# WaterLevel-STM8-V2.net
KiCad netlist of a schematic drawn in EAGLE
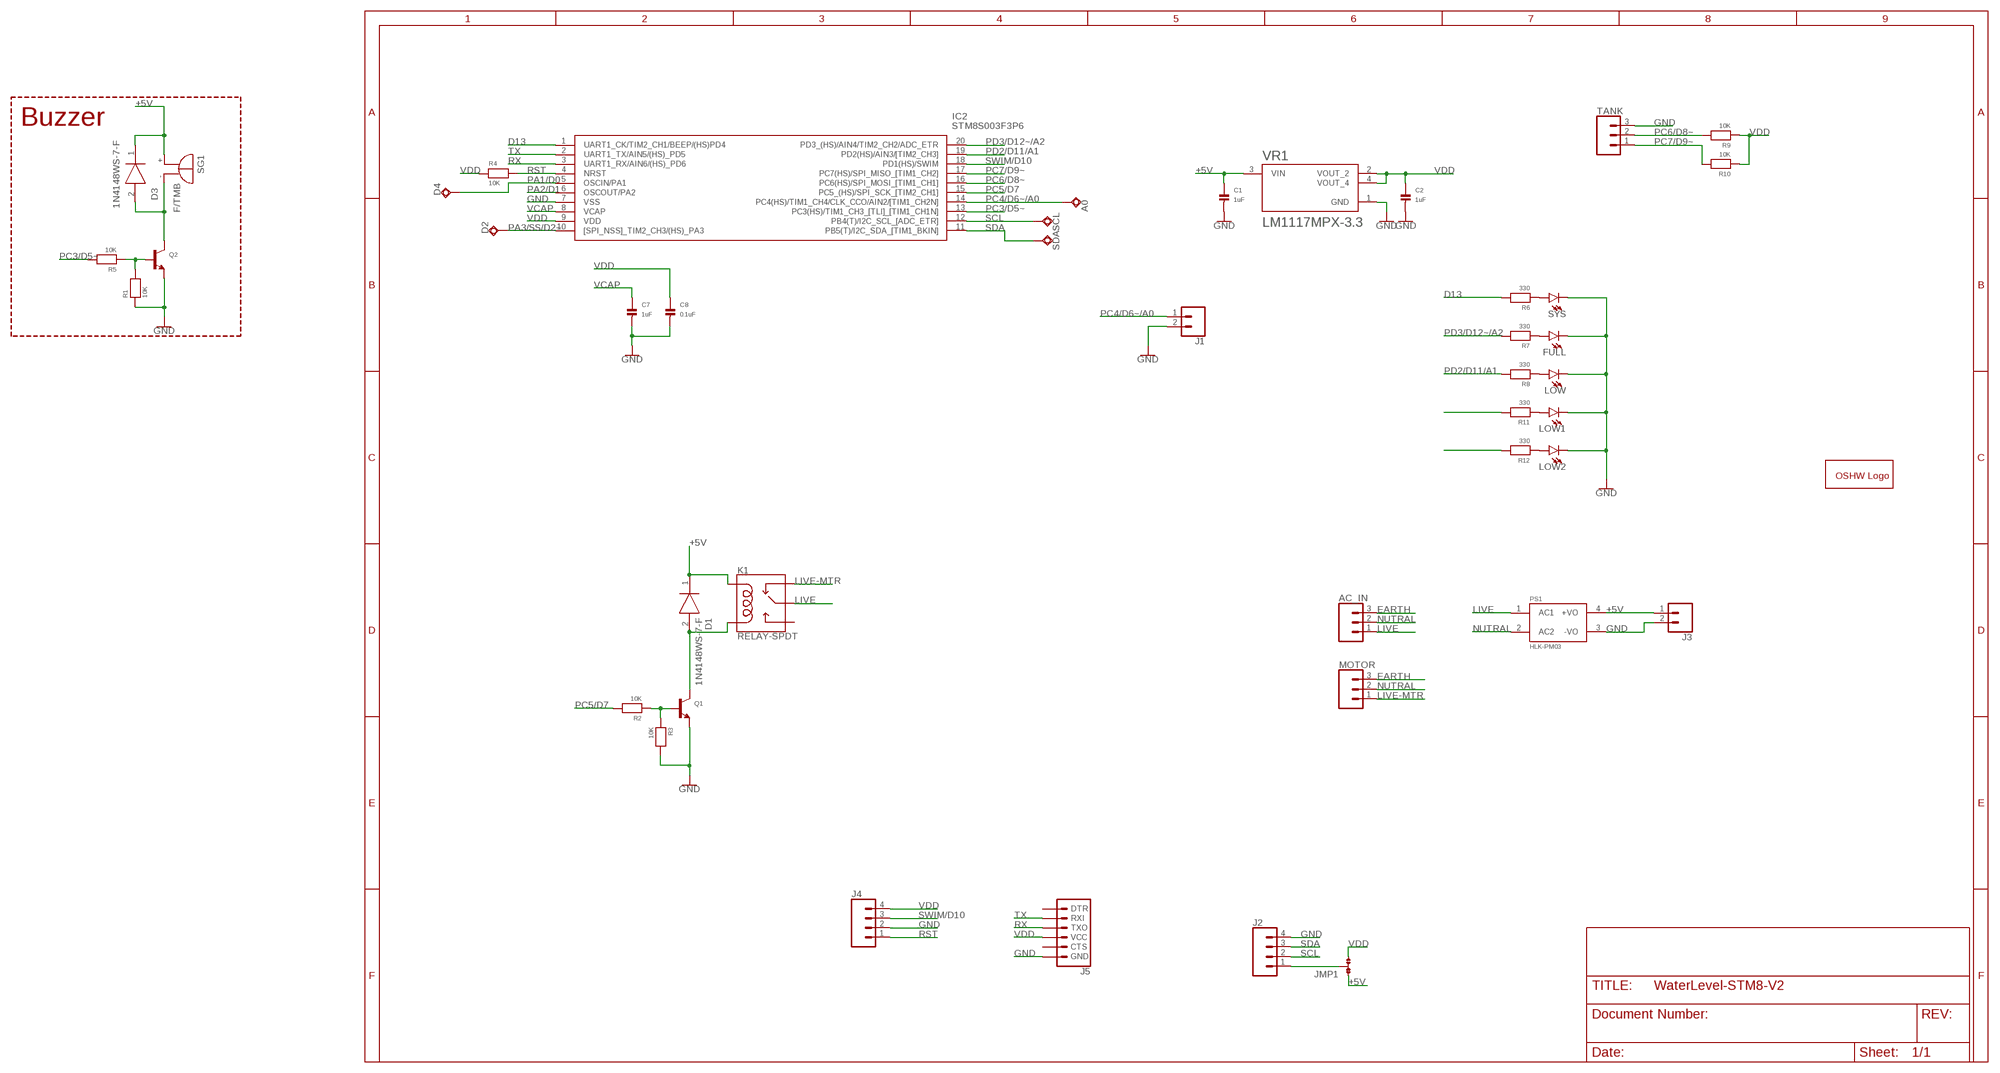
[diagram p0: schematic, sheet 1]

(export (version "E")
  (design (tool "Eeschema 10.0.6"))
  (components
    (comp (ref "A0")
      (value "TPSQTP20R")
      (footprint "eagle-import:TP20R")
      (libsource (lib "eagle-import") (part "TPSQTP20R"))
    )
    (comp (ref "AC_IN")
      (value "SCREW-CONN_03-SCREW-5MM")
      (footprint "eagle-import:SCREWTERMINAL-5MM-3")
      (libsource (lib "eagle-import") (part "SCREW-CONN_03-SCREW-5MM"))
    )
    (comp (ref "C1")
      (value "1uF")
      (footprint "eagle-import:C0805")
      (libsource (lib "eagle-import") (part "CAP_CERAMIC0805"))
    )
    (comp (ref "C2")
      (value "1uF")
      (footprint "eagle-import:C0805")
      (libsource (lib "eagle-import") (part "CAP_CERAMIC0805"))
    )
    (comp (ref "C7")
      (value "1uF")
      (footprint "eagle-import:C0805")
      (libsource (lib "eagle-import") (part "CAP_CERAMIC0805"))
    )
    (comp (ref "C8")
      (value "0.1uF")
      (footprint "eagle-import:C0805")
      (libsource (lib "eagle-import") (part "CAP_CERAMIC0805"))
    )
    (comp (ref "D1")
      (value "1N4148WS-7-F")
      (footprint "eagle-import:SOD2513X120N")
      (fields (field (name "MOUSER_PART_NUMBER") "621-1N4148WS-F"))
      (libsource (lib "eagle-import") (part "1N4148WS-7-F"))
    )
    (comp (ref "D2")
      (value "TPSQTP20R")
      (footprint "eagle-import:TP20R")
      (libsource (lib "eagle-import") (part "TPSQTP20R"))
    )
    (comp (ref "D3")
      (value "1N4148WS-7-F")
      (footprint "eagle-import:SOD2513X120N")
      (fields (field (name "MOUSER_PART_NUMBER") "621-1N4148WS-F"))
      (libsource (lib "eagle-import") (part "1N4148WS-7-F"))
    )
    (comp (ref "D4")
      (value "TPSQTP20R")
      (footprint "eagle-import:TP20R")
      (libsource (lib "eagle-import") (part "TPSQTP20R"))
    )
    (comp (ref "FULL")
      (value "LED-5MM-REC5MM")
      (footprint "eagle-import:LED_5MM")
      (libsource (lib "eagle-import") (part "LED-5MM-REC5MM"))
    )
    (comp (ref "GOLD_ORB_SM1")
      (value "OSHWLOGOLOGO16MM")
      (footprint "eagle-import:OSHW_16MM")
      (libsource (lib "eagle-import") (part "OSHWLOGOLOGO16MM"))
    )
    (comp (ref "IC2")
      (value "STM8S003F3P6")
      (footprint "eagle-import:SOP65P640X120-20N")
      (fields (field (name "MOUSER_PART_NUMBER") "511-STM8S003F3P6"))
      (libsource (lib "eagle-import") (part "STM8S003F3P6"))
    )
    (comp (ref "J1")
      (value "2PIN-2.54MM-POLARPOLAR")
      (footprint "eagle-import:MOLEX-1X2")
      (libsource (lib "eagle-import") (part "2PIN-2.54MM-POLARPOLAR"))
    )
    (comp (ref "J2")
      (value "CONN_04PTH")
      (footprint "eagle-import:1X04")
      (libsource (lib "eagle-import") (part "CONN_04PTH"))
    )
    (comp (ref "J3")
      (value "2PIN-2.54MM-POLARPOLAR")
      (footprint "eagle-import:MOLEX-1X2")
      (libsource (lib "eagle-import") (part "2PIN-2.54MM-POLARPOLAR"))
    )
    (comp (ref "J4")
      (value "CONN_04PTH")
      (footprint "eagle-import:1X04")
      (libsource (lib "eagle-import") (part "CONN_04PTH"))
    )
    (comp (ref "J5")
      (value "6_PIN_SERIAL_TARGETSILK")
      (footprint "eagle-import:6_PIN_SERIAL_TARGET_SIDE_W_SILK")
      (libsource (lib "eagle-import") (part "6_PIN_SERIAL_TARGETSILK"))
    )
    (comp (ref "JMP1")
      (value "JMP-3-NO")
      (footprint "eagle-import:JMP-3-NO")
      (libsource (lib "eagle-import") (part "JMP-3-NO"))
    )
    (comp (ref "K1")
      (value "RELAY-SPDT")
      (footprint "eagle-import:RELAY_G5LE")
      (libsource (lib "eagle-import") (part "RELAY-SPDT"))
    )
    (comp (ref "LOW")
      (value "LED-5MM-REC5MM")
      (footprint "eagle-import:LED_5MM")
      (libsource (lib "eagle-import") (part "LED-5MM-REC5MM"))
    )
    (comp (ref "LOW1")
      (value "LED-5MM-REC5MM")
      (footprint "eagle-import:LED_5MM")
      (libsource (lib "eagle-import") (part "LED-5MM-REC5MM"))
    )
    (comp (ref "LOW2")
      (value "LED-5MM-REC5MM")
      (footprint "eagle-import:LED_5MM")
      (libsource (lib "eagle-import") (part "LED-5MM-REC5MM"))
    )
    (comp (ref "MOTOR")
      (value "SCREW-CONN_03-SCREW-5MM")
      (footprint "eagle-import:SCREWTERMINAL-5MM-3")
      (libsource (lib "eagle-import") (part "SCREW-CONN_03-SCREW-5MM"))
    )
    (comp (ref "PS1")
      (value "HLK-PM03")
      (footprint "eagle-import:CONV_HLK-PM03")
      (fields (field (name "MF") "Hi-link"))
      (libsource (lib "eagle-import") (part "HLK-PM03"))
    )
    (comp (ref "Q1")
      (value "TRANSISTOR_NPNWIDE")
      (footprint "eagle-import:SOT23-WIDE")
      (libsource (lib "eagle-import") (part "TRANSISTOR_NPNWIDE"))
    )
    (comp (ref "Q2")
      (value "TRANSISTOR_NPNWIDE")
      (footprint "eagle-import:SOT23-WIDE")
      (libsource (lib "eagle-import") (part "TRANSISTOR_NPNWIDE"))
    )
    (comp (ref "R1")
      (value "10K")
      (footprint "eagle-import:R0805")
      (libsource (lib "eagle-import") (part "RESISTOR0805"))
    )
    (comp (ref "R2")
      (value "10K")
      (footprint "eagle-import:R0805")
      (libsource (lib "eagle-import") (part "RESISTOR0805"))
    )
    (comp (ref "R3")
      (value "10K")
      (footprint "eagle-import:R0805")
      (libsource (lib "eagle-import") (part "RESISTOR0805"))
    )
    (comp (ref "R4")
      (value "10K")
      (footprint "eagle-import:R0805")
      (libsource (lib "eagle-import") (part "RESISTOR0805"))
    )
    (comp (ref "R5")
      (value "10K")
      (footprint "eagle-import:R0805")
      (libsource (lib "eagle-import") (part "RESISTOR0805"))
    )
    (comp (ref "R6")
      (value "330")
      (footprint "eagle-import:R0805")
      (libsource (lib "eagle-import") (part "RESISTOR0805"))
    )
    (comp (ref "R7")
      (value "330")
      (footprint "eagle-import:R0805")
      (libsource (lib "eagle-import") (part "RESISTOR0805"))
    )
    (comp (ref "R8")
      (value "330")
      (footprint "eagle-import:R0805")
      (libsource (lib "eagle-import") (part "RESISTOR0805"))
    )
    (comp (ref "R9")
      (value "10K")
      (footprint "eagle-import:R0805")
      (libsource (lib "eagle-import") (part "RESISTOR0805"))
    )
    (comp (ref "R10")
      (value "10K")
      (footprint "eagle-import:R0805")
      (libsource (lib "eagle-import") (part "RESISTOR0805"))
    )
    (comp (ref "R11")
      (value "330")
      (footprint "eagle-import:R0805")
      (libsource (lib "eagle-import") (part "RESISTOR0805"))
    )
    (comp (ref "R12")
      (value "330")
      (footprint "eagle-import:R0805")
      (libsource (lib "eagle-import") (part "RESISTOR0805"))
    )
    (comp (ref "SCL")
      (value "TPSQTP20R")
      (footprint "eagle-import:TP20R")
      (libsource (lib "eagle-import") (part "TPSQTP20R"))
    )
    (comp (ref "SDA")
      (value "TPSQTP20R")
      (footprint "eagle-import:TP20R")
      (libsource (lib "eagle-import") (part "TPSQTP20R"))
    )
    (comp (ref "SG1")
      (value "F/TMB")
      (footprint "eagle-import:F_TMB")
      (libsource (lib "eagle-import") (part "F/TMB"))
    )
    (comp (ref "SYS")
      (value "LED-5MM-REC5MM")
      (footprint "eagle-import:LED_5MM")
      (libsource (lib "eagle-import") (part "LED-5MM-REC5MM"))
    )
    (comp (ref "TANK")
      (value "SCREW-CONN_03-SCREW-5MM")
      (footprint "eagle-import:SCREWTERMINAL-5MM-3")
      (libsource (lib "eagle-import") (part "SCREW-CONN_03-SCREW-5MM"))
    )
    (comp (ref "VR1")
      (value "LM1117MPX-3.3")
      (footprint "eagle-import:VREG_LM1117MPX-3.3")
      (fields (field (name "MF") "Texas Instruments"))
      (libsource (lib "eagle-import") (part "LM1117MPX-3.3"))
    )
  )
  (nets
    (net (code "1") (name "/+5V") (class "Default")
      (node (ref "C1") (pin "1") (pinfunction "P$1_1") (pintype "passive"))
      (node (ref "D1") (pin "1") (pinfunction "K_1") (pintype "bidirectional"))
      (node (ref "D3") (pin "1") (pinfunction "K_1") (pintype "bidirectional"))
      (node (ref "J3") (pin "1") (pinfunction "1_1") (pintype "passive"))
      (node (ref "JMP1") (pin "1") (pinfunction "1_1") (pintype "passive"))
      (node (ref "K1") (pin "2") (pinfunction "COIL1_2") (pintype "bidirectional"))
      (node (ref "PS1") (pin "4") (pinfunction "+VO_4") (pintype "output"))
      (node (ref "SG1") (pin "+") (pinfunction "+_+") (pintype "passive"))
      (node (ref "VR1") (pin "3") (pinfunction "VIN_3") (pintype "input"))
    )
    (net (code "2") (name "/D13") (class "Default")
      (node (ref "IC2") (pin "1") (pinfunction "UART1_CK/TIM2_CH1/BEEP/(HS)PD4_1") (pintype "bidirectional"))
      (node (ref "R6") (pin "2") (pinfunction "2_2") (pintype "passive"))
    )
    (net (code "3") (name "/EARTH") (class "Default")
      (node (ref "AC_IN") (pin "3") (pinfunction "3_3") (pintype "passive"))
      (node (ref "MOTOR") (pin "3") (pinfunction "3_3") (pintype "passive"))
    )
    (net (code "4") (name "/LIVE") (class "Default")
      (node (ref "AC_IN") (pin "1") (pinfunction "1_1") (pintype "passive"))
      (node (ref "K1") (pin "1") (pinfunction "MAIN_1") (pintype "bidirectional"))
      (node (ref "PS1") (pin "1") (pinfunction "AC1_1") (pintype "input"))
    )
    (net (code "5") (name "/LIVE-MTR") (class "Default")
      (node (ref "K1") (pin "4") (pinfunction "NC_4") (pintype "bidirectional"))
      (node (ref "MOTOR") (pin "1") (pinfunction "1_1") (pintype "passive"))
    )
    (net (code "6") (name "/NUTRAL") (class "Default")
      (node (ref "AC_IN") (pin "2") (pinfunction "2_2") (pintype "passive"))
      (node (ref "MOTOR") (pin "2") (pinfunction "2_2") (pintype "passive"))
      (node (ref "PS1") (pin "2") (pinfunction "AC2_2") (pintype "input"))
    )
    (net (code "7") (name "/PA1{slash}D0") (class "Default")
      (node (ref "D4") (pin "TP") (pinfunction "TP_TP") (pintype "input"))
      (node (ref "IC2") (pin "5") (pinfunction "OSCIN/PA1_5") (pintype "input"))
    )
    (net (code "8") (name "/PA2{slash}D1") (class "Default")
      (node (ref "IC2") (pin "6") (pinfunction "OSCOUT/PA2_6") (pintype "output"))
    )
    (net (code "9") (name "/PA3{slash}SS{slash}D2~{}") (class "Default")
      (node (ref "D2") (pin "TP") (pinfunction "TP_TP") (pintype "input"))
      (node (ref "IC2") (pin "10") (pinfunction "[SPI_NSS]_TIM2_CH3/(HS)_PA3_10") (pintype "bidirectional"))
    )
    (net (code "10") (name "/PC3{slash}D5~{}") (class "Default")
      (node (ref "IC2") (pin "13") (pinfunction "PC3(HS)/TIM1_CH3_[TLI]_[TIM1_CH1N]_13") (pintype "bidirectional"))
      (node (ref "R5") (pin "2") (pinfunction "2_2") (pintype "passive"))
    )
    (net (code "11") (name "/PC4{slash}D6~{{slash}A0}") (class "Default")
      (node (ref "A0") (pin "TP") (pinfunction "TP_TP") (pintype "input"))
      (node (ref "IC2") (pin "14") (pinfunction "PC4(HS)/TIM1_CH4/CLK_CCO/AIN2/[TIM1_CH2N]_14") (pintype "input"))
      (node (ref "J1") (pin "1") (pinfunction "1_1") (pintype "passive"))
    )
    (net (code "12") (name "/PC5{slash}D7") (class "Default")
      (node (ref "IC2") (pin "15") (pinfunction "PC5_(HS)/SPI_SCK_[TIM2_CH1]_15") (pintype "bidirectional"))
      (node (ref "R2") (pin "2") (pinfunction "2_2") (pintype "passive"))
    )
    (net (code "13") (name "/PC6{slash}D8~{}") (class "Default")
      (node (ref "IC2") (pin "16") (pinfunction "PC6(HS)/SPI_MOSI_[TIM1_CH1]_16") (pintype "bidirectional"))
      (node (ref "R9") (pin "2") (pinfunction "2_2") (pintype "passive"))
      (node (ref "TANK") (pin "2") (pinfunction "2_2") (pintype "passive"))
    )
    (net (code "14") (name "/PC7{slash}D9~{}") (class "Default")
      (node (ref "IC2") (pin "17") (pinfunction "PC7(HS)/SPI_MISO_[TIM1_CH2]_17") (pintype "bidirectional"))
      (node (ref "R10") (pin "2") (pinfunction "2_2") (pintype "passive"))
      (node (ref "TANK") (pin "1") (pinfunction "1_1") (pintype "passive"))
    )
    (net (code "15") (name "/PD2{slash}D11{slash}A1") (class "Default")
      (node (ref "IC2") (pin "19") (pinfunction "PD2(HS)/AIN3/[TIM2_CH3]_19") (pintype "input"))
      (node (ref "R8") (pin "2") (pinfunction "2_2") (pintype "passive"))
    )
    (net (code "16") (name "/PD3{slash}D12~{{slash}A2}") (class "Default")
      (node (ref "IC2") (pin "20") (pinfunction "PD3_(HS)/AIN4/TIM2_CH2/ADC_ETR_20") (pintype "input"))
      (node (ref "R7") (pin "2") (pinfunction "2_2") (pintype "passive"))
    )
    (net (code "17") (name "/RST") (class "Default")
      (node (ref "IC2") (pin "4") (pinfunction "NRST_4") (pintype "input"))
      (node (ref "J4") (pin "1") (pinfunction "1_1") (pintype "passive"))
      (node (ref "R4") (pin "2") (pinfunction "2_2") (pintype "passive"))
    )
    (net (code "18") (name "/RX") (class "Default")
      (node (ref "IC2") (pin "3") (pinfunction "UART1_RX/AIN6/(HS)_PD6_3") (pintype "input"))
      (node (ref "J5") (pin "P$2") (pinfunction "TXO_P$2") (pintype "passive"))
    )
    (net (code "19") (name "/SCL") (class "Default")
      (node (ref "IC2") (pin "12") (pinfunction "PB4(T)/I2C_SCL_[ADC_ETR]_12") (pintype "bidirectional"))
      (node (ref "J2") (pin "2") (pinfunction "2_2") (pintype "passive"))
      (node (ref "SCL") (pin "TP") (pinfunction "TP_TP") (pintype "input"))
    )
    (net (code "20") (name "/SDA") (class "Default")
      (node (ref "IC2") (pin "11") (pinfunction "PB5(T)/I2C_SDA_[TIM1_BKIN]_11") (pintype "input"))
      (node (ref "J2") (pin "3") (pinfunction "3_3") (pintype "passive"))
      (node (ref "SDA") (pin "TP") (pinfunction "TP_TP") (pintype "input"))
    )
    (net (code "21") (name "/SWIM{slash}D10") (class "Default")
      (node (ref "IC2") (pin "18") (pinfunction "PD1(HS)/SWIM_18") (pintype "bidirectional"))
      (node (ref "J4") (pin "3") (pinfunction "3_3") (pintype "passive"))
    )
    (net (code "22") (name "/TX") (class "Default")
      (node (ref "IC2") (pin "2") (pinfunction "UART1_TX/AIN5/(HS)_PD5_2") (pintype "input"))
      (node (ref "J5") (pin "P$3") (pinfunction "RXI_P$3") (pintype "passive"))
    )
    (net (code "23") (name "/VCAP") (class "Default")
      (node (ref "C7") (pin "1") (pinfunction "P$1_1") (pintype "passive"))
      (node (ref "IC2") (pin "8") (pinfunction "VCAP_8") (pintype "bidirectional"))
    )
    (net (code "24") (name "/VDD") (class "Default")
      (node (ref "C2") (pin "1") (pinfunction "P$1_1") (pintype "passive"))
      (node (ref "C8") (pin "1") (pinfunction "P$1_1") (pintype "passive"))
      (node (ref "IC2") (pin "9") (pinfunction "VDD_9") (pintype "power_in"))
      (node (ref "J4") (pin "4") (pinfunction "4_4") (pintype "passive"))
      (node (ref "J5") (pin "P$4") (pinfunction "VCC_P$4") (pintype "passive"))
      (node (ref "JMP1") (pin "3") (pinfunction "3_3") (pintype "passive"))
      (node (ref "R10") (pin "1") (pinfunction "1_1") (pintype "passive"))
      (node (ref "R4") (pin "1") (pinfunction "1_1") (pintype "passive"))
      (node (ref "R9") (pin "1") (pinfunction "1_1") (pintype "passive"))
      (node (ref "VR1") (pin "2") (pinfunction "VOUT_2_2") (pintype "output"))
      (node (ref "VR1") (pin "4") (pinfunction "VOUT_4_4") (pintype "output"))
    )
    (net (code "25") (name "GND") (class "Default")
      (node (ref "C1") (pin "2") (pinfunction "P$2_2") (pintype "passive"))
      (node (ref "C2") (pin "2") (pinfunction "P$2_2") (pintype "passive"))
      (node (ref "C7") (pin "2") (pinfunction "P$2_2") (pintype "passive"))
      (node (ref "C8") (pin "2") (pinfunction "P$2_2") (pintype "passive"))
      (node (ref "FULL") (pin "K") (pinfunction "C_K") (pintype "passive"))
      (node (ref "IC2") (pin "7") (pinfunction "VSS_7") (pintype "power_in"))
      (node (ref "J1") (pin "2") (pinfunction "2_2") (pintype "passive"))
      (node (ref "J2") (pin "4") (pinfunction "4_4") (pintype "passive"))
      (node (ref "J3") (pin "2") (pinfunction "2_2") (pintype "passive"))
      (node (ref "J4") (pin "2") (pinfunction "2_2") (pintype "passive"))
      (node (ref "J5") (pin "P$6") (pinfunction "GND_P$6") (pintype "passive"))
      (node (ref "LOW") (pin "K") (pinfunction "C_K") (pintype "passive"))
      (node (ref "LOW1") (pin "K") (pinfunction "C_K") (pintype "passive"))
      (node (ref "LOW2") (pin "K") (pinfunction "C_K") (pintype "passive"))
      (node (ref "PS1") (pin "3") (pinfunction "-VO_3") (pintype "output"))
      (node (ref "Q1") (pin "2") (pinfunction "E_2") (pintype "passive"))
      (node (ref "Q2") (pin "2") (pinfunction "E_2") (pintype "passive"))
      (node (ref "R1") (pin "1") (pinfunction "1_1") (pintype "passive"))
      (node (ref "R3") (pin "2") (pinfunction "2_2") (pintype "passive"))
      (node (ref "SYS") (pin "K") (pinfunction "C_K") (pintype "passive"))
      (node (ref "TANK") (pin "3") (pinfunction "3_3") (pintype "passive"))
      (node (ref "VR1") (pin "1") (pinfunction "GND_1") (pintype "power_in"))
    )
    (net (code "26") (name "Net-(D1-A)") (class "Default")
      (node (ref "D1") (pin "2") (pinfunction "A_2") (pintype "bidirectional"))
      (node (ref "K1") (pin "5") (pinfunction "COIL2_5") (pintype "bidirectional"))
      (node (ref "Q1") (pin "3") (pinfunction "C_3") (pintype "passive"))
    )
    (net (code "27") (name "Net-(D3-A)") (class "Default")
      (node (ref "D3") (pin "2") (pinfunction "A_2") (pintype "bidirectional"))
      (node (ref "Q2") (pin "3") (pinfunction "C_3") (pintype "passive"))
      (node (ref "SG1") (pin "-") (pinfunction "-_-") (pintype "passive"))
    )
    (net (code "28") (name "Net-(FULL-PadA)") (class "Default")
      (node (ref "FULL") (pin "A") (pinfunction "A_A") (pintype "passive"))
      (node (ref "R7") (pin "1") (pinfunction "1_1") (pintype "passive"))
    )
    (net (code "29") (name "Net-(J2-Pad1)") (class "Default")
      (node (ref "J2") (pin "1") (pinfunction "1_1") (pintype "passive"))
      (node (ref "JMP1") (pin "2") (pinfunction "2_2") (pintype "passive"))
    )
    (net (code "30") (name "Net-(LOW-PadA)") (class "Default")
      (node (ref "LOW") (pin "A") (pinfunction "A_A") (pintype "passive"))
      (node (ref "R8") (pin "1") (pinfunction "1_1") (pintype "passive"))
    )
    (net (code "31") (name "Net-(LOW1-PadA)") (class "Default")
      (node (ref "LOW1") (pin "A") (pinfunction "A_A") (pintype "passive"))
      (node (ref "R11") (pin "1") (pinfunction "1_1") (pintype "passive"))
    )
    (net (code "32") (name "Net-(LOW2-PadA)") (class "Default")
      (node (ref "LOW2") (pin "A") (pinfunction "A_A") (pintype "passive"))
      (node (ref "R12") (pin "1") (pinfunction "1_1") (pintype "passive"))
    )
    (net (code "33") (name "Net-(Q1-B)") (class "Default")
      (node (ref "Q1") (pin "1") (pinfunction "B_1") (pintype "passive"))
      (node (ref "R2") (pin "1") (pinfunction "1_1") (pintype "passive"))
      (node (ref "R3") (pin "1") (pinfunction "1_1") (pintype "passive"))
    )
    (net (code "34") (name "Net-(Q2-B)") (class "Default")
      (node (ref "Q2") (pin "1") (pinfunction "B_1") (pintype "passive"))
      (node (ref "R1") (pin "2") (pinfunction "2_2") (pintype "passive"))
      (node (ref "R5") (pin "1") (pinfunction "1_1") (pintype "passive"))
    )
    (net (code "35") (name "Net-(R6-Pad1)") (class "Default")
      (node (ref "R6") (pin "1") (pinfunction "1_1") (pintype "passive"))
      (node (ref "SYS") (pin "A") (pinfunction "A_A") (pintype "passive"))
    )
    (net (code "36") (name "unconnected-(J5-CTS-PadP$5)") (class "Default")
      (node (ref "J5") (pin "P$5") (pinfunction "CTS_P$5") (pintype "passive"))
    )
    (net (code "37") (name "unconnected-(J5-DTR-PadP$1)") (class "Default")
      (node (ref "J5") (pin "P$1") (pinfunction "DTR_P$1") (pintype "passive"))
    )
    (net (code "38") (name "unconnected-(K1-NO-Pad3)") (class "Default")
      (node (ref "K1") (pin "3") (pinfunction "NO_3") (pintype "bidirectional"))
    )
    (net (code "39") (name "unconnected-(R11-Pad2)") (class "Default")
      (node (ref "R11") (pin "2") (pinfunction "2_2") (pintype "passive"))
    )
    (net (code "40") (name "unconnected-(R12-Pad2)") (class "Default")
      (node (ref "R12") (pin "2") (pinfunction "2_2") (pintype "passive"))
    )
  )
)
